# PowerMeter_EADOG.net
KiCad netlist of a schematic drawn in EAGLE
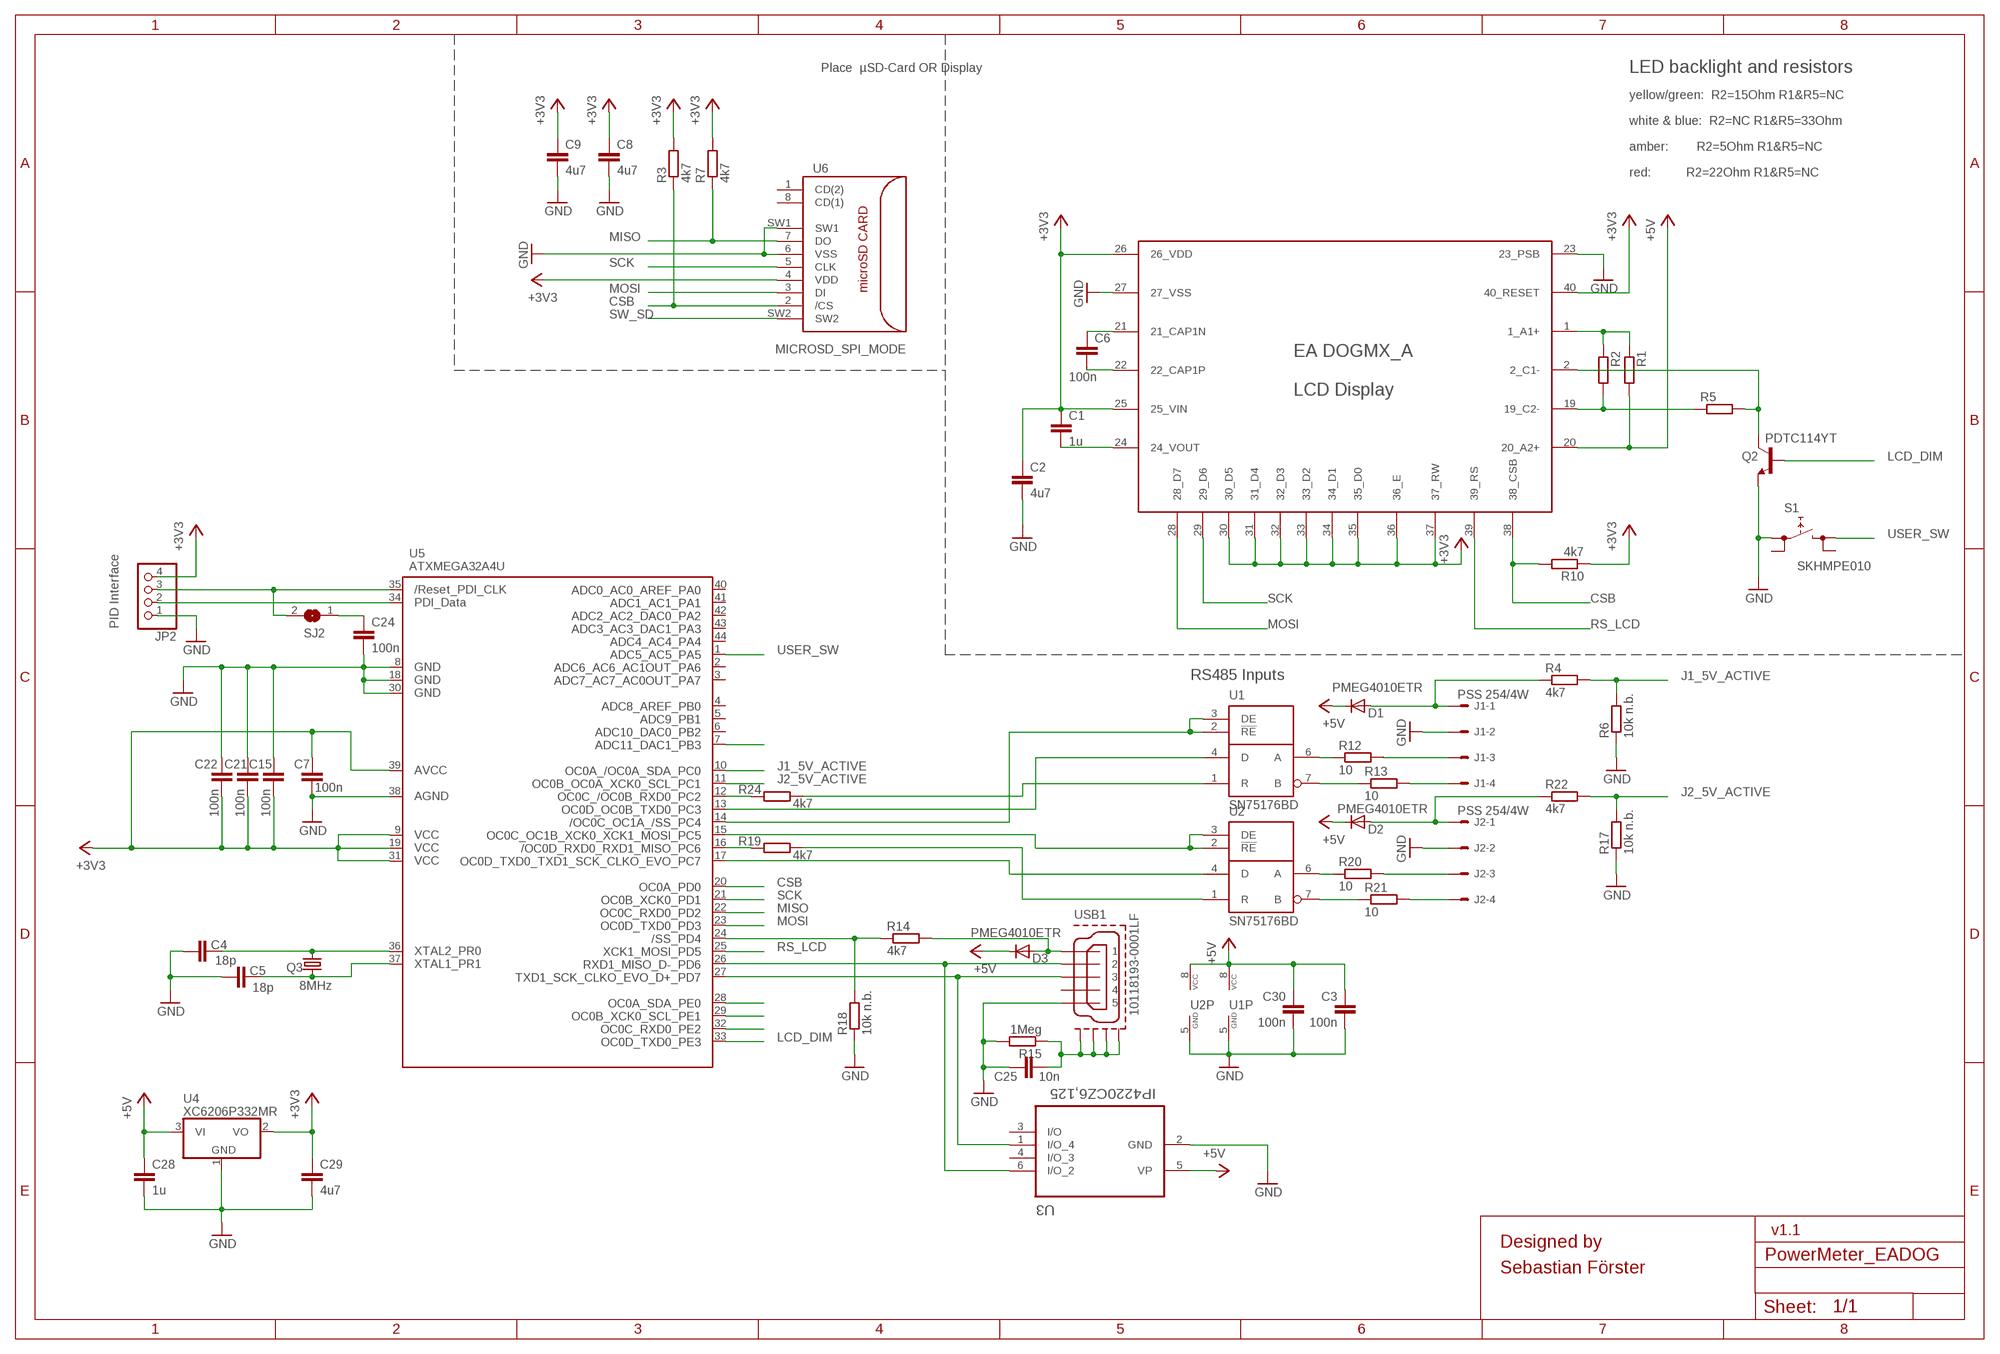
[diagram p0: schematic, sheet 1]

(export (version "E")
  (design (tool "Eeschema 10.0.6"))
  (components
    (comp (ref "C1")
      (value "1u")
      (footprint "eagle-import:C0603")
      (libsource (lib "eagle-import") (part "C-EUC0603"))
    )
    (comp (ref "C2")
      (value "4u7")
      (footprint "eagle-import:C0603")
      (libsource (lib "eagle-import") (part "C-EUC0603"))
    )
    (comp (ref "C3")
      (value "100n")
      (footprint "eagle-import:C0603")
      (libsource (lib "eagle-import") (part "C-EUC0603"))
    )
    (comp (ref "C4")
      (value "18p")
      (footprint "eagle-import:C0603")
      (libsource (lib "eagle-import") (part "C-EUC0603"))
    )
    (comp (ref "C5")
      (value "18p")
      (footprint "eagle-import:C0603")
      (libsource (lib "eagle-import") (part "C-EUC0603"))
    )
    (comp (ref "C6")
      (value "100n")
      (footprint "eagle-import:C0603")
      (libsource (lib "eagle-import") (part "C-EUC0603"))
    )
    (comp (ref "C7")
      (value "100n")
      (footprint "eagle-import:C0603")
      (libsource (lib "eagle-import") (part "C-EUC0603"))
    )
    (comp (ref "C8")
      (value "4u7")
      (footprint "eagle-import:C0603")
      (libsource (lib "eagle-import") (part "C-EUC0603"))
    )
    (comp (ref "C9")
      (value "4u7")
      (footprint "eagle-import:C0603")
      (libsource (lib "eagle-import") (part "C-EUC0603"))
    )
    (comp (ref "C15")
      (value "100n")
      (footprint "eagle-import:C0603")
      (libsource (lib "eagle-import") (part "C-EUC0603"))
    )
    (comp (ref "C21")
      (value "100n")
      (footprint "eagle-import:C0603")
      (libsource (lib "eagle-import") (part "C-EUC0603"))
    )
    (comp (ref "C22")
      (value "100n")
      (footprint "eagle-import:C0603")
      (libsource (lib "eagle-import") (part "C-EUC0603"))
    )
    (comp (ref "C24")
      (value "100n")
      (footprint "eagle-import:C0603")
      (libsource (lib "eagle-import") (part "C-EUC0603"))
    )
    (comp (ref "C25")
      (value "10n")
      (footprint "eagle-import:C0603")
      (libsource (lib "eagle-import") (part "C-EUC0603"))
    )
    (comp (ref "C28")
      (value "1u")
      (footprint "eagle-import:C0603")
      (libsource (lib "eagle-import") (part "C-EUC0603"))
    )
    (comp (ref "C29")
      (value "4u7")
      (footprint "eagle-import:C0603")
      (libsource (lib "eagle-import") (part "C-EUC0603"))
    )
    (comp (ref "C30")
      (value "100n")
      (footprint "eagle-import:C0603")
      (libsource (lib "eagle-import") (part "C-EUC0603"))
    )
    (comp (ref "D1")
      (value "PMEG4010ETR")
      (footprint "eagle-import:SOD123")
      (libsource (lib "eagle-import") (part "MBR0520LT"))
    )
    (comp (ref "D2")
      (value "PMEG4010ETR")
      (footprint "eagle-import:SOD123")
      (libsource (lib "eagle-import") (part "MBR0520LT"))
    )
    (comp (ref "D3")
      (value "PMEG4010ETR")
      (footprint "eagle-import:SOD123")
      (libsource (lib "eagle-import") (part "MBR0520LT"))
    )
    (comp (ref "J1")
      (value "PSS 254/4W")
      (footprint "eagle-import:6410-04")
      (libsource (lib "eagle-import") (part "22-?-0427-2041"))
    )
    (comp (ref "J2")
      (value "PSS 254/4W")
      (footprint "eagle-import:6410-04")
      (libsource (lib "eagle-import") (part "22-?-0427-2041"))
    )
    (comp (ref "JP2")
      (value "PINHD-1X4_2.00")
      (footprint "eagle-import:1X04M")
      (libsource (lib "eagle-import") (part "PINHD-1X4_2.00"))
    )
    (comp (ref "LCD1")
      (value "DOGM162X-AX")
      (footprint "eagle-import:EA_DOGM")
      (libsource (lib "eagle-import") (part "DOGM162X-AX"))
    )
    (comp (ref "Q2")
      (value "PDTC114YT")
      (footprint "eagle-import:SOT23")
      (libsource (lib "eagle-import") (part "BC848SMDALT1"))
    )
    (comp (ref "Q3")
      (value "8MHz")
      (footprint "eagle-import:HC49UP")
      (libsource (lib "eagle-import") (part "CRYSTALHC49UP"))
    )
    (comp (ref "R1")
      (value "R-EU_R0603")
      (footprint "eagle-import:R0603")
      (libsource (lib "eagle-import") (part "R-EU_R0603"))
    )
    (comp (ref "R2")
      (value "R-EU_R0603")
      (footprint "eagle-import:R0603")
      (libsource (lib "eagle-import") (part "R-EU_R0603"))
    )
    (comp (ref "R3")
      (value "4k7")
      (footprint "eagle-import:R0603")
      (libsource (lib "eagle-import") (part "R-EU_R0603"))
    )
    (comp (ref "R4")
      (value "4k7")
      (footprint "eagle-import:R0603")
      (libsource (lib "eagle-import") (part "R-EU_R0603"))
    )
    (comp (ref "R5")
      (value "R-EU_R0603")
      (footprint "eagle-import:R0603")
      (libsource (lib "eagle-import") (part "R-EU_R0603"))
    )
    (comp (ref "R6")
      (value "10k n.b.")
      (footprint "eagle-import:R0603")
      (libsource (lib "eagle-import") (part "R-EU_R0603"))
    )
    (comp (ref "R7")
      (value "4k7")
      (footprint "eagle-import:R0603")
      (libsource (lib "eagle-import") (part "R-EU_R0603"))
    )
    (comp (ref "R10")
      (value "4k7")
      (footprint "eagle-import:R0603")
      (libsource (lib "eagle-import") (part "R-EU_R0603"))
    )
    (comp (ref "R12")
      (value "10")
      (footprint "eagle-import:R0603")
      (libsource (lib "eagle-import") (part "R-EU_R0603"))
    )
    (comp (ref "R13")
      (value "10")
      (footprint "eagle-import:R0603")
      (libsource (lib "eagle-import") (part "R-EU_R0603"))
    )
    (comp (ref "R14")
      (value "4k7")
      (footprint "eagle-import:R0603")
      (libsource (lib "eagle-import") (part "R-EU_R0603"))
    )
    (comp (ref "R15")
      (value "1Meg")
      (footprint "eagle-import:R0603")
      (libsource (lib "eagle-import") (part "R-EU_R0603"))
    )
    (comp (ref "R17")
      (value "10k n.b.")
      (footprint "eagle-import:R0603")
      (libsource (lib "eagle-import") (part "R-EU_R0603"))
    )
    (comp (ref "R18")
      (value "10k n.b.")
      (footprint "eagle-import:R0603")
      (libsource (lib "eagle-import") (part "R-EU_R0603"))
    )
    (comp (ref "R19")
      (value "4k7")
      (footprint "eagle-import:R0603")
      (libsource (lib "eagle-import") (part "R-EU_R0603"))
    )
    (comp (ref "R20")
      (value "10")
      (footprint "eagle-import:R0603")
      (libsource (lib "eagle-import") (part "R-EU_R0603"))
    )
    (comp (ref "R21")
      (value "10")
      (footprint "eagle-import:R0603")
      (libsource (lib "eagle-import") (part "R-EU_R0603"))
    )
    (comp (ref "R22")
      (value "4k7")
      (footprint "eagle-import:R0603")
      (libsource (lib "eagle-import") (part "R-EU_R0603"))
    )
    (comp (ref "R24")
      (value "4k7")
      (footprint "eagle-import:R0603")
      (libsource (lib "eagle-import") (part "R-EU_R0603"))
    )
    (comp (ref "S1")
      (value "SKHMPE010")
      (footprint "eagle-import:SKHMPXE010")
      (libsource (lib "eagle-import") (part "SKHMPE010"))
    )
    (comp (ref "SJ2") (value "SJ") (footprint "eagle-import:SJ") (libsource (lib "eagle-import") (part "SJ")))
    (comp (ref "U1")
      (value "SN75176BD")
      (footprint "eagle-import:SO-08")
      (fields (field (name "MF") "TEXAS INSTRUMENTS") (field (name "MPN") "SN75ALS176AD"))
      (libsource (lib "eagle-import") (part "75ALS176DA"))
    )
    (comp (ref "U2")
      (value "SN75176BD")
      (footprint "eagle-import:SO-08")
      (fields (field (name "MF") "TEXAS INSTRUMENTS") (field (name "MPN") "SN75ALS176AD"))
      (libsource (lib "eagle-import") (part "75ALS176DA"))
    )
    (comp (ref "U3")
      (value "IP4220CZ6,125")
      (footprint "eagle-import:SOT95P275X110-6N")
      (fields (field (name "MPN") "IP4220CZ6"))
      (libsource (lib "eagle-import") (part "IP4220CZ6"))
    )
    (comp (ref "U4")
      (value "XC6206P332MR")
      (footprint "eagle-import:SOT23")
      (libsource (lib "eagle-import") (part "XC6206P332MR"))
    )
    (comp (ref "U5")
      (value "ATXMEGA32A4U")
      (footprint "eagle-import:TQFP44")
      (libsource (lib "eagle-import") (part "AVR_XMEGA_A4U_"))
    )
    (comp (ref "U6")
      (value "MICROSD_SPI_MODE")
      (footprint "eagle-import:MICRO_SD_CONNECTOR")
      (libsource (lib "eagle-import") (part "MICROSD_SPI_MODE"))
    )
    (comp (ref "USB1")
      (value "10118193-0001LF")
      (footprint "eagle-import:MOLEX-47364-0001")
      (libsource (lib "eagle-import") (part "MOLEX-47346-0001"))
    )
  )
  (nets
    (net (code "1") (name "+3V3") (class "Default")
      (node (ref "C1") (pin "1") (pinfunction "1_1") (pintype "passive"))
      (node (ref "C15") (pin "2") (pinfunction "2_2") (pintype "passive"))
      (node (ref "C2") (pin "1") (pinfunction "1_1") (pintype "passive"))
      (node (ref "C21") (pin "2") (pinfunction "2_2") (pintype "passive"))
      (node (ref "C22") (pin "2") (pinfunction "2_2") (pintype "passive"))
      (node (ref "C29") (pin "1") (pinfunction "1_1") (pintype "passive"))
      (node (ref "C7") (pin "1") (pinfunction "1_1") (pintype "passive"))
      (node (ref "C8") (pin "1") (pinfunction "1_1") (pintype "passive"))
      (node (ref "C9") (pin "1") (pinfunction "1_1") (pintype "passive"))
      (node (ref "JP2") (pin "4") (pinfunction "4_4") (pintype "passive"))
      (node (ref "LCD1") (pin "25") (pinfunction "25_VIN_25") (pintype "bidirectional"))
      (node (ref "LCD1") (pin "26") (pinfunction "26_VDD_26") (pintype "bidirectional"))
      (node (ref "LCD1") (pin "30") (pinfunction "30_D5_30") (pintype "bidirectional"))
      (node (ref "LCD1") (pin "31") (pinfunction "31_D4_31") (pintype "bidirectional"))
      (node (ref "LCD1") (pin "32") (pinfunction "32_D3_32") (pintype "bidirectional"))
      (node (ref "LCD1") (pin "33") (pinfunction "33_D2_33") (pintype "bidirectional"))
      (node (ref "LCD1") (pin "34") (pinfunction "34_D1_34") (pintype "bidirectional"))
      (node (ref "LCD1") (pin "35") (pinfunction "35_D0_35") (pintype "bidirectional"))
      (node (ref "LCD1") (pin "36") (pinfunction "36_E_36") (pintype "bidirectional"))
      (node (ref "LCD1") (pin "37") (pinfunction "37_RW_37") (pintype "bidirectional"))
      (node (ref "LCD1") (pin "40") (pinfunction "40_RESET_40") (pintype "bidirectional"))
      (node (ref "R10") (pin "1") (pinfunction "1_1") (pintype "passive"))
      (node (ref "R3") (pin "2") (pinfunction "2_2") (pintype "passive"))
      (node (ref "R7") (pin "2") (pinfunction "2_2") (pintype "passive"))
      (node (ref "U4") (pin "2") (pinfunction "VO_2") (pintype "passive"))
      (node (ref "U5") (pin "19") (pinfunction "VCC2_19") (pintype "bidirectional"))
      (node (ref "U5") (pin "31") (pinfunction "VCC3_31") (pintype "bidirectional"))
      (node (ref "U5") (pin "39") (pinfunction "AVCC_39") (pintype "bidirectional"))
      (node (ref "U5") (pin "9") (pinfunction "VCC1_9") (pintype "bidirectional"))
      (node (ref "U6") (pin "4") (pinfunction "VDD_4") (pintype "bidirectional"))
    )
    (net (code "2") (name "+5V") (class "Default")
      (node (ref "C28") (pin "1") (pinfunction "1_1") (pintype "passive"))
      (node (ref "C3") (pin "1") (pinfunction "1_1") (pintype "passive"))
      (node (ref "C30") (pin "1") (pinfunction "1_1") (pintype "passive"))
      (node (ref "D1") (pin "C") (pinfunction "C_C") (pintype "passive"))
      (node (ref "D2") (pin "C") (pinfunction "C_C") (pintype "passive"))
      (node (ref "D3") (pin "C") (pinfunction "C_C") (pintype "passive"))
      (node (ref "LCD1") (pin "20") (pinfunction "20_A2+_20") (pintype "bidirectional"))
      (node (ref "R1") (pin "2") (pinfunction "2_2") (pintype "passive"))
      (node (ref "U1") (pin "8") (pinfunction "VCC_8") (pintype "power_in"))
      (node (ref "U2") (pin "8") (pinfunction "VCC_8") (pintype "power_in"))
      (node (ref "U3") (pin "5") (pinfunction "VP_5") (pintype "power_in"))
      (node (ref "U4") (pin "3") (pinfunction "VI_3") (pintype "input"))
    )
    (net (code "3") (name "/CSB") (class "Default")
      (node (ref "LCD1") (pin "38") (pinfunction "38_CSB_38") (pintype "bidirectional"))
      (node (ref "R10") (pin "2") (pinfunction "2_2") (pintype "passive"))
      (node (ref "R3") (pin "1") (pinfunction "1_1") (pintype "passive"))
      (node (ref "U5") (pin "20") (pinfunction "PD0_20") (pintype "bidirectional"))
      (node (ref "U6") (pin "2") (pinfunction "/CS_2") (pintype "bidirectional"))
    )
    (net (code "4") (name "/J1_5V_ACTIVE") (class "Default")
      (node (ref "R4") (pin "2") (pinfunction "2_2") (pintype "passive"))
      (node (ref "R6") (pin "2") (pinfunction "2_2") (pintype "passive"))
      (node (ref "U5") (pin "10") (pinfunction "PC0_10") (pintype "bidirectional"))
    )
    (net (code "5") (name "/J2_5V_ACTIVE") (class "Default")
      (node (ref "R17") (pin "2") (pinfunction "2_2") (pintype "passive"))
      (node (ref "R22") (pin "2") (pinfunction "2_2") (pintype "passive"))
      (node (ref "U5") (pin "11") (pinfunction "PC1_11") (pintype "bidirectional"))
    )
    (net (code "6") (name "/LCD_DIM") (class "Default")
      (node (ref "Q2") (pin "1") (pinfunction "B_1") (pintype "passive"))
      (node (ref "U5") (pin "33") (pinfunction "PE3_33") (pintype "bidirectional"))
    )
    (net (code "7") (name "/MISO") (class "Default")
      (node (ref "R7") (pin "1") (pinfunction "1_1") (pintype "passive"))
      (node (ref "U5") (pin "22") (pinfunction "PD2_22") (pintype "bidirectional"))
      (node (ref "U6") (pin "7") (pinfunction "DO_7") (pintype "bidirectional"))
    )
    (net (code "8") (name "/MOSI") (class "Default")
      (node (ref "LCD1") (pin "28") (pinfunction "28_D7_28") (pintype "bidirectional"))
      (node (ref "U5") (pin "23") (pinfunction "PD3_23") (pintype "bidirectional"))
      (node (ref "U6") (pin "3") (pinfunction "DI_3") (pintype "bidirectional"))
    )
    (net (code "9") (name "/RS_LCD") (class "Default")
      (node (ref "LCD1") (pin "39") (pinfunction "39_RS_39") (pintype "bidirectional"))
      (node (ref "U5") (pin "25") (pinfunction "PD5_25") (pintype "bidirectional"))
    )
    (net (code "10") (name "/SCK") (class "Default")
      (node (ref "LCD1") (pin "29") (pinfunction "29_D6_29") (pintype "bidirectional"))
      (node (ref "U5") (pin "21") (pinfunction "PD1_21") (pintype "bidirectional"))
      (node (ref "U6") (pin "5") (pinfunction "CLK_5") (pintype "bidirectional"))
    )
    (net (code "11") (name "/SW_SD") (class "Default")
      (node (ref "U5") (pin "28") (pinfunction "PE0_28") (pintype "bidirectional"))
      (node (ref "U6") (pin "SW2") (pinfunction "SW2_SW2") (pintype "bidirectional"))
    )
    (net (code "12") (name "/USER_SW") (class "Default")
      (node (ref "S1") (pin "3") (pinfunction "2.3_3") (pintype "passive"))
      (node (ref "U5") (pin "1") (pinfunction "PA5_1") (pintype "bidirectional"))
    )
    (net (code "13") (name "GND") (class "Default")
      (node (ref "C15") (pin "1") (pinfunction "1_1") (pintype "passive"))
      (node (ref "C2") (pin "2") (pinfunction "2_2") (pintype "passive"))
      (node (ref "C21") (pin "1") (pinfunction "1_1") (pintype "passive"))
      (node (ref "C22") (pin "1") (pinfunction "1_1") (pintype "passive"))
      (node (ref "C24") (pin "2") (pinfunction "2_2") (pintype "passive"))
      (node (ref "C25") (pin "1") (pinfunction "1_1") (pintype "passive"))
      (node (ref "C28") (pin "2") (pinfunction "2_2") (pintype "passive"))
      (node (ref "C29") (pin "2") (pinfunction "2_2") (pintype "passive"))
      (node (ref "C3") (pin "2") (pinfunction "2_2") (pintype "passive"))
      (node (ref "C30") (pin "2") (pinfunction "2_2") (pintype "passive"))
      (node (ref "C4") (pin "1") (pinfunction "1_1") (pintype "passive"))
      (node (ref "C5") (pin "1") (pinfunction "1_1") (pintype "passive"))
      (node (ref "C7") (pin "2") (pinfunction "2_2") (pintype "passive"))
      (node (ref "C8") (pin "2") (pinfunction "2_2") (pintype "passive"))
      (node (ref "C9") (pin "2") (pinfunction "2_2") (pintype "passive"))
      (node (ref "J1") (pin "2") (pinfunction "S_2") (pintype "passive"))
      (node (ref "J2") (pin "2") (pinfunction "S_2") (pintype "passive"))
      (node (ref "JP2") (pin "1") (pinfunction "1_1") (pintype "passive"))
      (node (ref "LCD1") (pin "23") (pinfunction "23_PSB_23") (pintype "bidirectional"))
      (node (ref "LCD1") (pin "27") (pinfunction "27_VSS_27") (pintype "bidirectional"))
      (node (ref "Q2") (pin "2") (pinfunction "E_2") (pintype "passive"))
      (node (ref "R15") (pin "2") (pinfunction "2_2") (pintype "passive"))
      (node (ref "R17") (pin "1") (pinfunction "1_1") (pintype "passive"))
      (node (ref "R18") (pin "1") (pinfunction "1_1") (pintype "passive"))
      (node (ref "R6") (pin "1") (pinfunction "1_1") (pintype "passive"))
      (node (ref "S1") (pin "1") (pinfunction "1.1_1") (pintype "passive"))
      (node (ref "U1") (pin "5") (pinfunction "GND_5") (pintype "power_in"))
      (node (ref "U2") (pin "5") (pinfunction "GND_5") (pintype "power_in"))
      (node (ref "U3") (pin "2") (pinfunction "GND_2") (pintype "passive"))
      (node (ref "U4") (pin "1") (pinfunction "GND_1") (pintype "passive"))
      (node (ref "U5") (pin "18") (pinfunction "GND2_18") (pintype "bidirectional"))
      (node (ref "U5") (pin "30") (pinfunction "GND3_30") (pintype "bidirectional"))
      (node (ref "U5") (pin "38") (pinfunction "AGND_38") (pintype "bidirectional"))
      (node (ref "U5") (pin "8") (pinfunction "GND1_8") (pintype "bidirectional"))
      (node (ref "U6") (pin "6") (pinfunction "VSS_6") (pintype "bidirectional"))
      (node (ref "U6") (pin "SW1") (pinfunction "SW1_SW1") (pintype "bidirectional"))
      (node (ref "USB1") (pin "5") (pinfunction "5_5") (pintype "input"))
    )
    (net (code "14") (name "Net-(C24-Pad1)") (class "Default")
      (node (ref "C24") (pin "1") (pinfunction "1_1") (pintype "passive"))
      (node (ref "SJ2") (pin "1") (pinfunction "1_1") (pintype "passive"))
    )
    (net (code "15") (name "Net-(C25-Pad2)") (class "Default")
      (node (ref "C25") (pin "2") (pinfunction "2_2") (pintype "passive"))
      (node (ref "R15") (pin "1") (pinfunction "1_1") (pintype "passive"))
      (node (ref "USB1") (pin "GND1") (pinfunction "GND1_GND1") (pintype "bidirectional"))
      (node (ref "USB1") (pin "GND2") (pinfunction "GND2_GND2") (pintype "bidirectional"))
      (node (ref "USB1") (pin "GND3") (pinfunction "GND3_GND3") (pintype "bidirectional"))
      (node (ref "USB1") (pin "GND4") (pinfunction "GND4_GND4") (pintype "bidirectional"))
    )
    (net (code "16") (name "Net-(D3-PadA)") (class "Default")
      (node (ref "D3") (pin "A") (pinfunction "A_A") (pintype "passive"))
      (node (ref "R14") (pin "2") (pinfunction "2_2") (pintype "passive"))
      (node (ref "USB1") (pin "1") (pinfunction "1_1") (pintype "input"))
    )
    (net (code "17") (name "Net-(J1A-S)") (class "Default")
      (node (ref "D1") (pin "A") (pinfunction "A_A") (pintype "passive"))
      (node (ref "J1") (pin "1") (pinfunction "S_1") (pintype "passive"))
      (node (ref "R4") (pin "1") (pinfunction "1_1") (pintype "passive"))
    )
    (net (code "18") (name "Net-(J1C-S)") (class "Default")
      (node (ref "J1") (pin "3") (pinfunction "S_3") (pintype "passive"))
      (node (ref "R12") (pin "2") (pinfunction "2_2") (pintype "passive"))
    )
    (net (code "19") (name "Net-(J1D-S)") (class "Default")
      (node (ref "J1") (pin "4") (pinfunction "S_4") (pintype "passive"))
      (node (ref "R13") (pin "2") (pinfunction "2_2") (pintype "passive"))
    )
    (net (code "20") (name "Net-(J2A-S)") (class "Default")
      (node (ref "D2") (pin "A") (pinfunction "A_A") (pintype "passive"))
      (node (ref "J2") (pin "1") (pinfunction "S_1") (pintype "passive"))
      (node (ref "R22") (pin "1") (pinfunction "1_1") (pintype "passive"))
    )
    (net (code "21") (name "Net-(J2C-S)") (class "Default")
      (node (ref "J2") (pin "3") (pinfunction "S_3") (pintype "passive"))
      (node (ref "R20") (pin "2") (pinfunction "2_2") (pintype "passive"))
    )
    (net (code "22") (name "Net-(J2D-S)") (class "Default")
      (node (ref "J2") (pin "4") (pinfunction "S_4") (pintype "passive"))
      (node (ref "R21") (pin "2") (pinfunction "2_2") (pintype "passive"))
    )
    (net (code "23") (name "Net-(LCD1-1_A1+)") (class "Default")
      (node (ref "LCD1") (pin "1") (pinfunction "1_A1+_1") (pintype "bidirectional"))
      (node (ref "R1") (pin "1") (pinfunction "1_1") (pintype "passive"))
      (node (ref "R2") (pin "1") (pinfunction "1_1") (pintype "passive"))
    )
    (net (code "24") (name "Net-(LCD1-2_C1-)") (class "Default")
      (node (ref "LCD1") (pin "2") (pinfunction "2_C1-_2") (pintype "bidirectional"))
      (node (ref "Q2") (pin "3") (pinfunction "C_3") (pintype "passive"))
      (node (ref "R5") (pin "2") (pinfunction "2_2") (pintype "passive"))
    )
    (net (code "25") (name "Net-(LCD1-19_C2-)") (class "Default")
      (node (ref "LCD1") (pin "19") (pinfunction "19_C2-_19") (pintype "bidirectional"))
      (node (ref "R2") (pin "2") (pinfunction "2_2") (pintype "passive"))
      (node (ref "R5") (pin "1") (pinfunction "1_1") (pintype "passive"))
    )
    (net (code "26") (name "Net-(LCD1-21_CAP1N)") (class "Default")
      (node (ref "C6") (pin "1") (pinfunction "1_1") (pintype "passive"))
      (node (ref "LCD1") (pin "21") (pinfunction "21_CAP1N_21") (pintype "bidirectional"))
    )
    (net (code "27") (name "Net-(LCD1-22_CAP1P)") (class "Default")
      (node (ref "C6") (pin "2") (pinfunction "2_2") (pintype "passive"))
      (node (ref "LCD1") (pin "22") (pinfunction "22_CAP1P_22") (pintype "bidirectional"))
    )
    (net (code "28") (name "Net-(LCD1-24_VOUT)") (class "Default")
      (node (ref "C1") (pin "2") (pinfunction "2_2") (pintype "passive"))
      (node (ref "LCD1") (pin "24") (pinfunction "24_VOUT_24") (pintype "bidirectional"))
    )
    (net (code "29") (name "Net-(U1A-A)") (class "Default")
      (node (ref "R12") (pin "1") (pinfunction "1_1") (pintype "passive"))
      (node (ref "U1") (pin "6") (pinfunction "A_6") (pintype "bidirectional"))
    )
    (net (code "30") (name "Net-(U1A-B)") (class "Default")
      (node (ref "R13") (pin "1") (pinfunction "1_1") (pintype "passive"))
      (node (ref "U1") (pin "7") (pinfunction "B_7") (pintype "bidirectional"))
    )
    (net (code "31") (name "Net-(U1A-D)") (class "Default")
      (node (ref "U1") (pin "4") (pinfunction "D_4") (pintype "input"))
      (node (ref "U5") (pin "13") (pinfunction "PC3_13") (pintype "bidirectional"))
    )
    (net (code "32") (name "Net-(U1A-DE)") (class "Default")
      (node (ref "U1") (pin "2") (pinfunction "~{RE}_2") (pintype "input"))
      (node (ref "U1") (pin "3") (pinfunction "DE_3") (pintype "input"))
      (node (ref "U5") (pin "14") (pinfunction "PC4_14") (pintype "bidirectional"))
    )
    (net (code "33") (name "Net-(U1A-R)") (class "Default")
      (node (ref "R24") (pin "2") (pinfunction "2_2") (pintype "passive"))
      (node (ref "U1") (pin "1") (pinfunction "R_1") (pintype "output"))
    )
    (net (code "34") (name "Net-(U2A-A)") (class "Default")
      (node (ref "R20") (pin "1") (pinfunction "1_1") (pintype "passive"))
      (node (ref "U2") (pin "6") (pinfunction "A_6") (pintype "bidirectional"))
    )
    (net (code "35") (name "Net-(U2A-B)") (class "Default")
      (node (ref "R21") (pin "1") (pinfunction "1_1") (pintype "passive"))
      (node (ref "U2") (pin "7") (pinfunction "B_7") (pintype "bidirectional"))
    )
    (net (code "36") (name "Net-(U2A-D)") (class "Default")
      (node (ref "U2") (pin "4") (pinfunction "D_4") (pintype "input"))
      (node (ref "U5") (pin "17") (pinfunction "PC7_17") (pintype "bidirectional"))
    )
    (net (code "37") (name "Net-(U2A-DE)") (class "Default")
      (node (ref "U2") (pin "2") (pinfunction "~{RE}_2") (pintype "input"))
      (node (ref "U2") (pin "3") (pinfunction "DE_3") (pintype "input"))
      (node (ref "U5") (pin "15") (pinfunction "PC5_15") (pintype "bidirectional"))
    )
    (net (code "38") (name "Net-(U2A-R)") (class "Default")
      (node (ref "R19") (pin "2") (pinfunction "2_2") (pintype "passive"))
      (node (ref "U2") (pin "1") (pinfunction "R_1") (pintype "output"))
    )
    (net (code "39") (name "Net-(U3-I{slash}O_2)") (class "Default")
      (node (ref "U3") (pin "6") (pinfunction "I/O_2_6") (pintype "bidirectional"))
      (node (ref "U5") (pin "26") (pinfunction "PD6_26") (pintype "bidirectional"))
      (node (ref "USB1") (pin "2") (pinfunction "2_2") (pintype "input"))
    )
    (net (code "40") (name "Net-(U3-I{slash}O_4)") (class "Default")
      (node (ref "U3") (pin "1") (pinfunction "I/O_4_1") (pintype "bidirectional"))
      (node (ref "U5") (pin "27") (pinfunction "PD7_27") (pintype "bidirectional"))
      (node (ref "USB1") (pin "3") (pinfunction "3_3") (pintype "input"))
    )
    (net (code "41") (name "Net-(U5-PC2)") (class "Default")
      (node (ref "R24") (pin "1") (pinfunction "1_1") (pintype "passive"))
      (node (ref "U5") (pin "12") (pinfunction "PC2_12") (pintype "bidirectional"))
    )
    (net (code "42") (name "Net-(U5-PC6)") (class "Default")
      (node (ref "R19") (pin "1") (pinfunction "1_1") (pintype "passive"))
      (node (ref "U5") (pin "16") (pinfunction "PC6_16") (pintype "bidirectional"))
    )
    (net (code "43") (name "Net-(U5-PD4)") (class "Default")
      (node (ref "R14") (pin "1") (pinfunction "1_1") (pintype "passive"))
      (node (ref "R18") (pin "2") (pinfunction "2_2") (pintype "passive"))
      (node (ref "U5") (pin "24") (pinfunction "PD4_24") (pintype "bidirectional"))
    )
    (net (code "44") (name "Net-(U5-PDI_DATA)") (class "Default")
      (node (ref "JP2") (pin "2") (pinfunction "2_2") (pintype "passive"))
      (node (ref "U5") (pin "34") (pinfunction "PDI_DATA_34") (pintype "bidirectional"))
    )
    (net (code "45") (name "Net-(U5-PR0)") (class "Default")
      (node (ref "C4") (pin "2") (pinfunction "2_2") (pintype "passive"))
      (node (ref "Q3") (pin "1") (pinfunction "1_1") (pintype "passive"))
      (node (ref "U5") (pin "36") (pinfunction "PR0_36") (pintype "bidirectional"))
    )
    (net (code "46") (name "Net-(U5-PR1)") (class "Default")
      (node (ref "C5") (pin "2") (pinfunction "2_2") (pintype "passive"))
      (node (ref "Q3") (pin "2") (pinfunction "2_2") (pintype "passive"))
      (node (ref "U5") (pin "37") (pinfunction "PR1_37") (pintype "bidirectional"))
    )
    (net (code "47") (name "Net-(U5-RESET)") (class "Default")
      (node (ref "JP2") (pin "3") (pinfunction "3_3") (pintype "passive"))
      (node (ref "SJ2") (pin "2") (pinfunction "2_2") (pintype "passive"))
      (node (ref "U5") (pin "35") (pinfunction "RESET_35") (pintype "bidirectional"))
    )
    (net (code "48") (name "unconnected-(S1-1.2-Pad2)") (class "Default")
      (node (ref "S1") (pin "2") (pinfunction "1.2_2") (pintype "passive"))
    )
    (net (code "49") (name "unconnected-(S1-2.4-Pad4)") (class "Default")
      (node (ref "S1") (pin "4") (pinfunction "2.4_4") (pintype "passive"))
    )
    (net (code "50") (name "unconnected-(U3-I{slash}O-Pad3)") (class "Default")
      (node (ref "U3") (pin "3") (pinfunction "I/O_3") (pintype "bidirectional"))
    )
    (net (code "51") (name "unconnected-(U3-I{slash}O_3-Pad4)") (class "Default")
      (node (ref "U3") (pin "4") (pinfunction "I/O_3_4") (pintype "bidirectional"))
    )
    (net (code "52") (name "unconnected-(U5-PA0-Pad40)") (class "Default")
      (node (ref "U5") (pin "40") (pinfunction "PA0_40") (pintype "bidirectional"))
    )
    (net (code "53") (name "unconnected-(U5-PA1-Pad41)") (class "Default")
      (node (ref "U5") (pin "41") (pinfunction "PA1_41") (pintype "bidirectional"))
    )
    (net (code "54") (name "unconnected-(U5-PA2-Pad42)") (class "Default")
      (node (ref "U5") (pin "42") (pinfunction "PA2_42") (pintype "bidirectional"))
    )
    (net (code "55") (name "unconnected-(U5-PA3-Pad43)") (class "Default")
      (node (ref "U5") (pin "43") (pinfunction "PA3_43") (pintype "bidirectional"))
    )
    (net (code "56") (name "unconnected-(U5-PA4-Pad44)") (class "Default")
      (node (ref "U5") (pin "44") (pinfunction "PA4_44") (pintype "bidirectional"))
    )
    (net (code "57") (name "unconnected-(U5-PA6-Pad2)") (class "Default")
      (node (ref "U5") (pin "2") (pinfunction "PA6_2") (pintype "bidirectional"))
    )
    (net (code "58") (name "unconnected-(U5-PA7-Pad3)") (class "Default")
      (node (ref "U5") (pin "3") (pinfunction "PA7_3") (pintype "bidirectional"))
    )
    (net (code "59") (name "unconnected-(U5-PB0-Pad4)") (class "Default")
      (node (ref "U5") (pin "4") (pinfunction "PB0_4") (pintype "bidirectional"))
    )
    (net (code "60") (name "unconnected-(U5-PB1-Pad5)") (class "Default")
      (node (ref "U5") (pin "5") (pinfunction "PB1_5") (pintype "bidirectional"))
    )
    (net (code "61") (name "unconnected-(U5-PB2-Pad6)") (class "Default")
      (node (ref "U5") (pin "6") (pinfunction "PB2_6") (pintype "bidirectional"))
    )
    (net (code "62") (name "unconnected-(U5-PB3-Pad7)") (class "Default")
      (node (ref "U5") (pin "7") (pinfunction "PB3_7") (pintype "bidirectional"))
    )
    (net (code "63") (name "unconnected-(U5-PE1-Pad29)") (class "Default")
      (node (ref "U5") (pin "29") (pinfunction "PE1_29") (pintype "bidirectional"))
    )
    (net (code "64") (name "unconnected-(U5-PE2-Pad32)") (class "Default")
      (node (ref "U5") (pin "32") (pinfunction "PE2_32") (pintype "bidirectional"))
    )
    (net (code "65") (name "unconnected-(U6-CD(1)-Pad8)") (class "Default")
      (node (ref "U6") (pin "8") (pinfunction "CD(1)_8") (pintype "bidirectional"))
    )
    (net (code "66") (name "unconnected-(U6-CD(2)-Pad1)") (class "Default")
      (node (ref "U6") (pin "1") (pinfunction "CD(2)_1") (pintype "bidirectional"))
    )
    (net (code "67") (name "unconnected-(USB1-Pad4)") (class "Default")
      (node (ref "USB1") (pin "4") (pinfunction "4_4") (pintype "input"))
    )
  )
)
